# power.net
KiCad netlist of a schematic drawn in Altium Designer
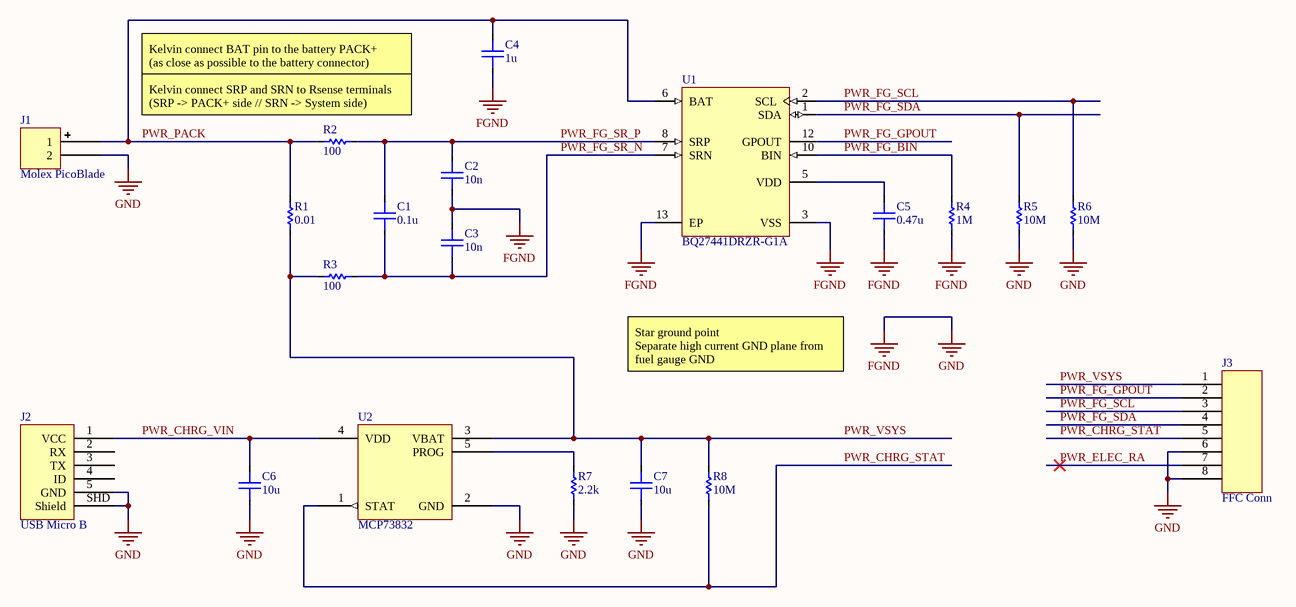
[diagram p0: power.SchDoc]

(export (version "E")
  (design (tool "Eeschema 10.0.6"))
  (components
    (comp (ref "C1")
      (value "0.1u")
      (footprint "C0402")
      (description "Capacitor")
      (libsource (lib "misc") (part "Capacitor"))
    )
    (comp (ref "C2")
      (value "10n")
      (footprint "C0402")
      (description "Capacitor")
      (libsource (lib "misc") (part "Capacitor"))
    )
    (comp (ref "C3")
      (value "10n")
      (footprint "C0402")
      (description "Capacitor")
      (libsource (lib "misc") (part "Capacitor"))
    )
    (comp (ref "C4")
      (value "1u")
      (footprint "C0402")
      (description "Capacitor")
      (libsource (lib "misc") (part "Capacitor"))
    )
    (comp (ref "C5")
      (value "0.47u")
      (footprint "C0402")
      (description "Capacitor")
      (libsource (lib "misc") (part "Capacitor"))
    )
    (comp (ref "C6")
      (value "10u")
      (footprint "C0603")
      (description "Capacitor")
      (libsource (lib "misc") (part "Capacitor"))
    )
    (comp (ref "C7")
      (value "10u")
      (footprint "C0603")
      (description "Capacitor")
      (libsource (lib "misc") (part "Capacitor"))
    )
    (comp (ref "J1")
      (value "Molex PicoBlade")
      (footprint "Molex 53261-0271")
      (description "Conn - Battery, PicoBlade, Male, 2 Pin, SMD, Right Angle")
      (libsource (lib "ecg-go") (part "Molex 53261-0271"))
    )
    (comp (ref "J2")
      (value "USB Micro B")
      (footprint "Amphenol FCI 10118192-0001LF")
      (description "Conn - USB Micro B, SMD, Receptacle")
      (libsource (lib "ecg-go") (part "Amphenol FCI 10118192-0001LF"))
    )
    (comp (ref "J3")
      (value "FFC Conn")
      (footprint "WE68610814122")
      (description "Conn - FFC, 8 Pin, 1 mm Pitch, Top Contacts, SMD, Right Angle, Slide Lock")
      (libsource (lib "ecg-go") (part "WE68610814122"))
    )
    (comp (ref "R1")
      (value "0.01")
      (footprint "R0603")
      (description "Resistor")
      (libsource (lib "misc") (part "Resistor"))
    )
    (comp (ref "R2")
      (value "100")
      (footprint "R0402")
      (description "Resistor")
      (libsource (lib "misc") (part "Resistor"))
    )
    (comp (ref "R3")
      (value "100")
      (footprint "R0402")
      (description "Resistor")
      (libsource (lib "misc") (part "Resistor"))
    )
    (comp (ref "R4")
      (value "1M")
      (footprint "R0402")
      (description "Resistor")
      (libsource (lib "misc") (part "Resistor"))
    )
    (comp (ref "R5")
      (value "10M")
      (footprint "R0402")
      (description "Resistor")
      (libsource (lib "misc") (part "Resistor"))
    )
    (comp (ref "R6")
      (value "10M")
      (footprint "R0402")
      (description "Resistor")
      (libsource (lib "misc") (part "Resistor"))
    )
    (comp (ref "R7")
      (value "2.2k")
      (footprint "R0402")
      (description "Resistor")
      (libsource (lib "misc") (part "Resistor"))
    )
    (comp (ref "R8")
      (value "10M")
      (footprint "R0402")
      (description "Resistor")
      (libsource (lib "misc") (part "Resistor"))
    )
    (comp (ref "U1")
      (value "BQ27441DRZR-G1A")
      (footprint "BQ27441DRZx-G1A")
      (description "IC - Fuel Gauge, System-Side Impedance Track")
      (fields (field (name "PARTNUMBER") "BQ27410DRZR-G1A") (field (name "MANUFACTURER") "Texas Instruments"))
      (libsource (lib "ecg-go") (part "BQ27441DRZR-G1A"))
    )
    (comp (ref "U2")
      (value "MCP73832")
      (footprint "MCP7383X")
      (description "IC - Battery Charger, Single Cell Li-Ion/LiPo, 0.5A")
      (libsource (lib "ecg-go") (part "MCP73832"))
    )
  )
  (nets
    (net (code "1") (name "/PWR_CHRG_STAT") (class "Default")
      (node (ref "J3") (pin "5") (pinfunction "5_5") (pintype "passive"))
      (node (ref "R8") (pin "1") (pinfunction "1_1") (pintype "passive"))
      (node (ref "U2") (pin "1") (pinfunction "STAT_1") (pintype "output"))
    )
    (net (code "2") (name "/PWR_CHRG_VIN") (class "Default")
      (node (ref "C6") (pin "2") (pinfunction "2_2") (pintype "passive"))
      (node (ref "J2") (pin "1") (pinfunction "VCC_1") (pintype "power_in"))
      (node (ref "U2") (pin "4") (pinfunction "VDD_4") (pintype "power_in"))
    )
    (net (code "4") (name "/PWR_ELEC_RA") (class "Default")
      (node (ref "J3") (pin "7") (pinfunction "7_7") (pintype "passive"))
    )
    (net (code "5") (name "/PWR_FG_BIN") (class "Default")
      (node (ref "R4") (pin "2") (pinfunction "2_2") (pintype "passive"))
      (node (ref "U1") (pin "10") (pinfunction "BIN_10") (pintype "input"))
    )
    (net (code "6") (name "/PWR_FG_GPOUT") (class "Default")
      (node (ref "J3") (pin "2") (pinfunction "2_2") (pintype "passive"))
      (node (ref "U1") (pin "12") (pinfunction "GPOUT_12") (pintype "open_collector"))
    )
    (net (code "7") (name "/PWR_FG_SCL") (class "Default")
      (node (ref "J3") (pin "3") (pinfunction "3_3") (pintype "passive"))
      (node (ref "R6") (pin "2") (pinfunction "2_2") (pintype "passive"))
      (node (ref "U1") (pin "2") (pinfunction "SCL_2") (pintype "input"))
    )
    (net (code "8") (name "/PWR_FG_SDA") (class "Default")
      (node (ref "J3") (pin "4") (pinfunction "4_4") (pintype "passive"))
      (node (ref "R5") (pin "2") (pinfunction "2_2") (pintype "passive"))
      (node (ref "U1") (pin "1") (pinfunction "SDA_1") (pintype "bidirectional"))
    )
    (net (code "9") (name "/PWR_FG_SR_N") (class "Default")
      (node (ref "C1") (pin "1") (pinfunction "1_1") (pintype "passive"))
      (node (ref "C3") (pin "1") (pinfunction "1_1") (pintype "passive"))
      (node (ref "R3") (pin "2") (pinfunction "2_2") (pintype "passive"))
      (node (ref "U1") (pin "7") (pinfunction "SRN_7") (pintype "input"))
    )
    (net (code "10") (name "/PWR_FG_SR_P") (class "Default")
      (node (ref "C1") (pin "2") (pinfunction "2_2") (pintype "passive"))
      (node (ref "C2") (pin "2") (pinfunction "2_2") (pintype "passive"))
      (node (ref "R2") (pin "2") (pinfunction "2_2") (pintype "passive"))
      (node (ref "U1") (pin "8") (pinfunction "SRP_8") (pintype "input"))
    )
    (net (code "11") (name "/PWR_PACK") (class "Default")
      (node (ref "C4") (pin "2") (pinfunction "2_2") (pintype "passive"))
      (node (ref "J1") (pin "1") (pinfunction "1_1") (pintype "passive"))
      (node (ref "R1") (pin "1") (pinfunction "1_1") (pintype "passive"))
      (node (ref "R2") (pin "1") (pinfunction "1_1") (pintype "passive"))
      (node (ref "U1") (pin "6") (pinfunction "BAT_6") (pintype "input"))
    )
    (net (code "12") (name "/PWR_VSYS") (class "Default")
      (node (ref "C7") (pin "2") (pinfunction "2_2") (pintype "passive"))
      (node (ref "J3") (pin "1") (pinfunction "1_1") (pintype "passive"))
      (node (ref "R1") (pin "2") (pinfunction "2_2") (pintype "passive"))
      (node (ref "R3") (pin "1") (pinfunction "1_1") (pintype "passive"))
      (node (ref "R8") (pin "2") (pinfunction "2_2") (pintype "passive"))
      (node (ref "U2") (pin "3") (pinfunction "VBAT_3") (pintype "power_in"))
    )
    (net (code "13") (name "FGND") (class "Default")
      (node (ref "C2") (pin "1") (pinfunction "1_1") (pintype "passive"))
      (node (ref "C3") (pin "2") (pinfunction "2_2") (pintype "passive"))
      (node (ref "C4") (pin "1") (pinfunction "1_1") (pintype "passive"))
      (node (ref "C5") (pin "1") (pinfunction "1_1") (pintype "passive"))
      (node (ref "C6") (pin "1") (pinfunction "1_1") (pintype "passive"))
      (node (ref "C7") (pin "1") (pinfunction "1_1") (pintype "passive"))
      (node (ref "J1") (pin "2") (pinfunction "2_2") (pintype "passive"))
      (node (ref "J2") (pin "5") (pinfunction "GND_5") (pintype "power_in"))
      (node (ref "J2") (pin "SHD") (pinfunction "Shield_SHD") (pintype "power_in"))
      (node (ref "J3") (pin "6") (pinfunction "6_6") (pintype "passive"))
      (node (ref "J3") (pin "8") (pinfunction "8_8") (pintype "passive"))
      (node (ref "R4") (pin "1") (pinfunction "1_1") (pintype "passive"))
      (node (ref "R5") (pin "1") (pinfunction "1_1") (pintype "passive"))
      (node (ref "R6") (pin "1") (pinfunction "1_1") (pintype "passive"))
      (node (ref "R7") (pin "2") (pinfunction "2_2") (pintype "passive"))
      (node (ref "U1") (pin "13") (pinfunction "EP_13") (pintype "passive"))
      (node (ref "U1") (pin "3") (pinfunction "VSS_3") (pintype "power_in"))
      (node (ref "U2") (pin "2") (pinfunction "GND_2") (pintype "power_in"))
    )
    (net (code "14") (name "Net-(U1-VDD)") (class "Default")
      (node (ref "C5") (pin "2") (pinfunction "2_2") (pintype "passive"))
      (node (ref "U1") (pin "5") (pinfunction "VDD_5") (pintype "power_in"))
    )
    (net (code "15") (name "Net-(U2-PROG)") (class "Default")
      (node (ref "R7") (pin "1") (pinfunction "1_1") (pintype "passive"))
      (node (ref "U2") (pin "5") (pinfunction "PROG_5") (pintype "passive"))
    )
    (net (code "16") (name "unconnected-(J2-ID-Pad4)") (class "Default")
      (node (ref "J2") (pin "4") (pinfunction "ID_4") (pintype "passive"))
    )
    (net (code "17") (name "unconnected-(J2-RX-Pad2)") (class "Default")
      (node (ref "J2") (pin "2") (pinfunction "RX_2") (pintype "passive"))
    )
    (net (code "18") (name "unconnected-(J2-TX-Pad3)") (class "Default")
      (node (ref "J2") (pin "3") (pinfunction "TX_3") (pintype "passive"))
    )
  )
)
